# 02-MCU.net
KiCad netlist of a schematic drawn in Altium Designer
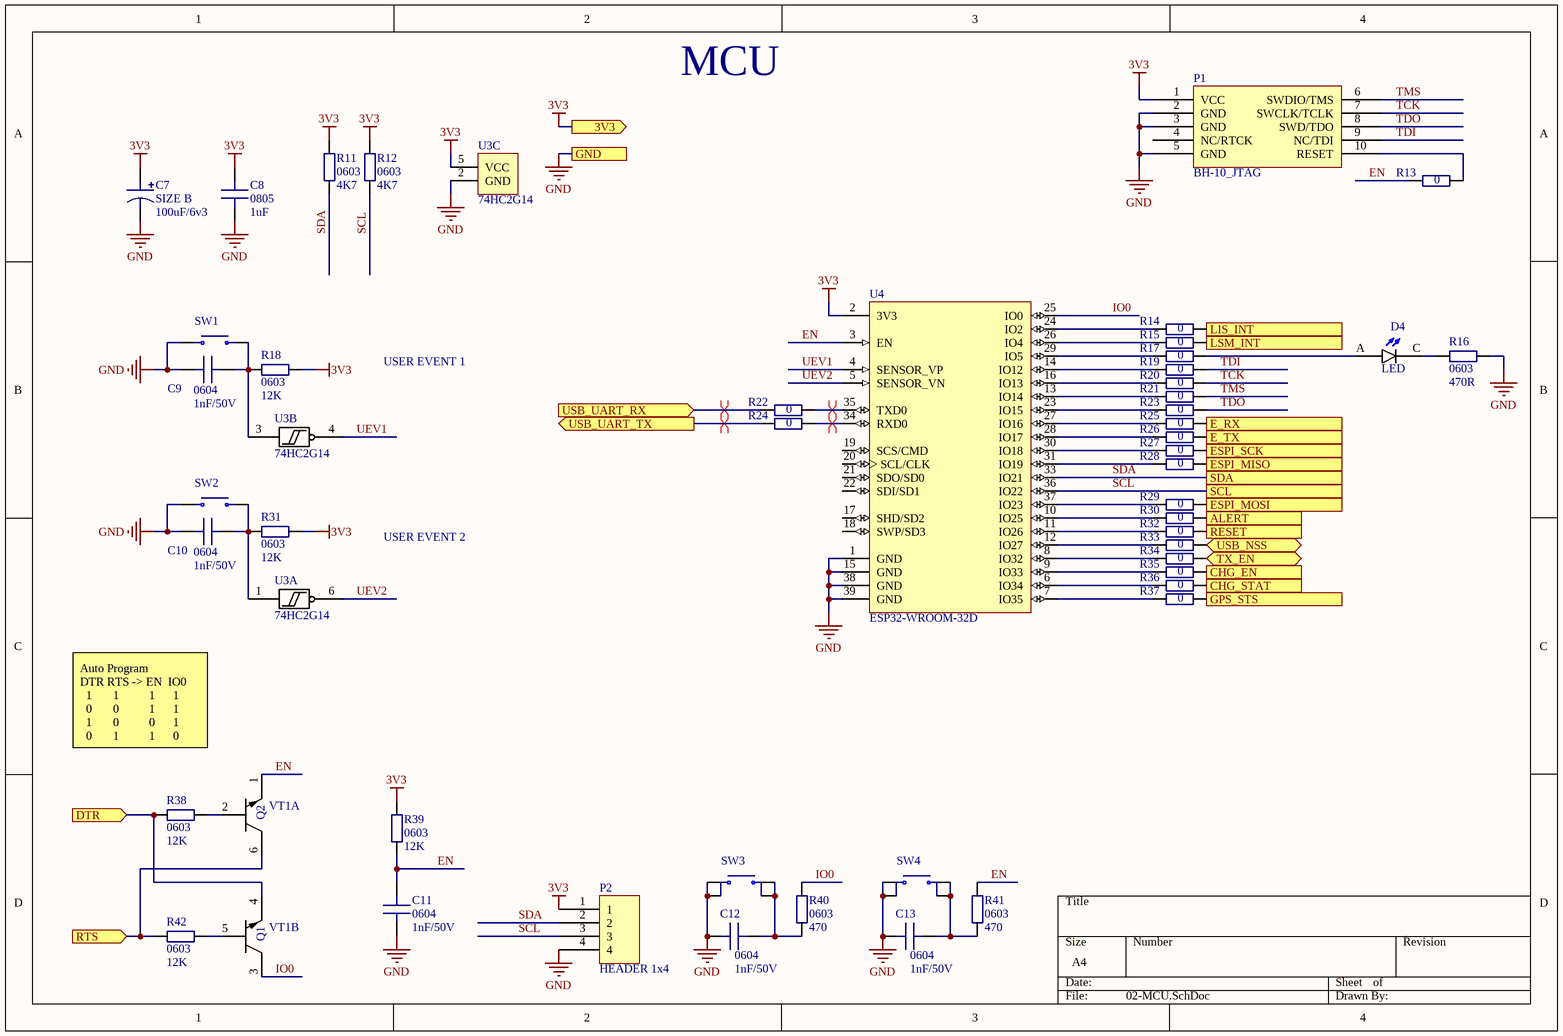
[diagram p0: 02-MCU.SchDoc]

(export (version "E")
  (design (tool "Eeschema 10.0.6"))
  (components
    (comp (ref "C7")
      (value "100uF/6v3")
      (footprint "CAP_SIZE_B")
      (description "General capacitor")
      (fields (field (name "SIZE") "SIZE B"))
      (libsource (lib "ComponentsLib") (part "C_GEN_POL_"))
    )
    (comp (ref "C8")
      (value "1uF")
      (footprint "C0805")
      (description "General capacitor")
      (fields (field (name "SIZE") "0805"))
      (libsource (lib "ComponentsLib") (part "C_GEN_NONPOL"))
    )
    (comp (ref "C9")
      (value "1nF/50V")
      (footprint "C0604")
      (description "General capacitor")
      (fields (field (name "SIZE") "0604"))
      (libsource (lib "ComponentsLib") (part "C_GEN_NONPOL"))
    )
    (comp (ref "C10")
      (value "1nF/50V")
      (footprint "C0604")
      (description "General capacitor")
      (fields (field (name "SIZE") "0604"))
      (libsource (lib "ComponentsLib") (part "C_GEN_NONPOL"))
    )
    (comp (ref "C11")
      (value "1nF/50V")
      (footprint "C0604")
      (description "General capacitor")
      (fields (field (name "SIZE") "0604"))
      (libsource (lib "ComponentsLib") (part "C_GEN_NONPOL"))
    )
    (comp (ref "C12")
      (value "1nF/50V")
      (footprint "C0604")
      (description "General capacitor")
      (fields (field (name "SIZE") "0604"))
      (libsource (lib "ComponentsLib") (part "C_GEN_NONPOL"))
    )
    (comp (ref "C13")
      (value "1nF/50V")
      (footprint "C0604")
      (description "General capacitor")
      (fields (field (name "SIZE") "0604"))
      (libsource (lib "ComponentsLib") (part "C_GEN_NONPOL"))
    )
    (comp (ref "D4")
      (value "LED")
      (footprint "LED_0604")
      (description "Led General")
      (fields (field (name "MF") "Dialight") (field (name "MP") "598-8140-107F"))
      (libsource (lib "ComponentsLib") (part "LED"))
    )
    (comp (ref "P1")
      (value "BH-10_JTAG")
      (footprint "BH-10R")
      (libsource (lib "ComponentsLib") (part "BH-10_JTAG"))
    )
    (comp (ref "P2")
      (value "HEADER 1x4")
      (footprint "HEADER 1x4 2.54")
      (libsource (lib "ComponentsLib") (part "HEADER 1x4"))
    )
    (comp (ref "R11")
      (value "~")
      (footprint "R0604")
      (description "Resistor General")
      (fields (field (name "SIZE") "0603") (field (name "RESISTANCE") "4K7"))
      (libsource (lib "ComponentsLib") (part "R_GENERAL"))
    )
    (comp (ref "R12")
      (value "~")
      (footprint "R0604")
      (description "Resistor General")
      (fields (field (name "SIZE") "0603") (field (name "RESISTANCE") "4K7"))
      (libsource (lib "ComponentsLib") (part "R_GENERAL"))
    )
    (comp (ref "R13")
      (value "~")
      (footprint "R0402")
      (description "Resistor General")
      (fields (field (name "RESISTANCE") "0"))
      (libsource (lib "ComponentsLib") (part "R_GENERAL"))
    )
    (comp (ref "R14")
      (value "~")
      (footprint "R0402")
      (description "Resistor General")
      (fields (field (name "RESISTANCE") "0"))
      (libsource (lib "ComponentsLib") (part "R_GENERAL"))
    )
    (comp (ref "R15")
      (value "~")
      (footprint "R0402")
      (description "Resistor General")
      (fields (field (name "RESISTANCE") "0"))
      (libsource (lib "ComponentsLib") (part "R_GENERAL"))
    )
    (comp (ref "R16")
      (value "~")
      (footprint "R0604")
      (description "Resistor General")
      (fields (field (name "SIZE") "0603") (field (name "RESISTANCE") "470R"))
      (libsource (lib "ComponentsLib") (part "R_GENERAL"))
    )
    (comp (ref "R17")
      (value "~")
      (footprint "R0402")
      (description "Resistor General")
      (fields (field (name "RESISTANCE") "0"))
      (libsource (lib "ComponentsLib") (part "R_GENERAL"))
    )
    (comp (ref "R18")
      (value "~")
      (footprint "R0604")
      (description "Resistor General")
      (fields (field (name "SIZE") "0603") (field (name "RESISTANCE") "12K"))
      (libsource (lib "ComponentsLib") (part "R_GENERAL"))
    )
    (comp (ref "R19")
      (value "~")
      (footprint "R0402")
      (description "Resistor General")
      (fields (field (name "RESISTANCE") "0"))
      (libsource (lib "ComponentsLib") (part "R_GENERAL"))
    )
    (comp (ref "R20")
      (value "~")
      (footprint "R0402")
      (description "Resistor General")
      (fields (field (name "RESISTANCE") "0"))
      (libsource (lib "ComponentsLib") (part "R_GENERAL"))
    )
    (comp (ref "R21")
      (value "~")
      (footprint "R0402")
      (description "Resistor General")
      (fields (field (name "RESISTANCE") "0"))
      (libsource (lib "ComponentsLib") (part "R_GENERAL"))
    )
    (comp (ref "R22")
      (value "~")
      (footprint "R0402")
      (description "Resistor General")
      (fields (field (name "RESISTANCE") "0"))
      (libsource (lib "ComponentsLib") (part "R_GENERAL"))
    )
    (comp (ref "R23")
      (value "~")
      (footprint "R0402")
      (description "Resistor General")
      (fields (field (name "RESISTANCE") "0"))
      (libsource (lib "ComponentsLib") (part "R_GENERAL"))
    )
    (comp (ref "R24")
      (value "~")
      (footprint "R0402")
      (description "Resistor General")
      (fields (field (name "RESISTANCE") "0"))
      (libsource (lib "ComponentsLib") (part "R_GENERAL"))
    )
    (comp (ref "R25")
      (value "~")
      (footprint "R0402")
      (description "Resistor General")
      (fields (field (name "RESISTANCE") "0"))
      (libsource (lib "ComponentsLib") (part "R_GENERAL"))
    )
    (comp (ref "R26")
      (value "~")
      (footprint "R0402")
      (description "Resistor General")
      (fields (field (name "RESISTANCE") "0"))
      (libsource (lib "ComponentsLib") (part "R_GENERAL"))
    )
    (comp (ref "R27")
      (value "~")
      (footprint "R0402")
      (description "Resistor General")
      (fields (field (name "RESISTANCE") "0"))
      (libsource (lib "ComponentsLib") (part "R_GENERAL"))
    )
    (comp (ref "R28")
      (value "~")
      (footprint "R0402")
      (description "Resistor General")
      (fields (field (name "RESISTANCE") "0"))
      (libsource (lib "ComponentsLib") (part "R_GENERAL"))
    )
    (comp (ref "R29")
      (value "~")
      (footprint "R0402")
      (description "Resistor General")
      (fields (field (name "RESISTANCE") "0"))
      (libsource (lib "ComponentsLib") (part "R_GENERAL"))
    )
    (comp (ref "R30")
      (value "~")
      (footprint "R0402")
      (description "Resistor General")
      (fields (field (name "RESISTANCE") "0"))
      (libsource (lib "ComponentsLib") (part "R_GENERAL"))
    )
    (comp (ref "R31")
      (value "~")
      (footprint "R0604")
      (description "Resistor General")
      (fields (field (name "SIZE") "0603") (field (name "RESISTANCE") "12K"))
      (libsource (lib "ComponentsLib") (part "R_GENERAL"))
    )
    (comp (ref "R32")
      (value "~")
      (footprint "R0402")
      (description "Resistor General")
      (fields (field (name "RESISTANCE") "0"))
      (libsource (lib "ComponentsLib") (part "R_GENERAL"))
    )
    (comp (ref "R33")
      (value "~")
      (footprint "R0402")
      (description "Resistor General")
      (fields (field (name "RESISTANCE") "0"))
      (libsource (lib "ComponentsLib") (part "R_GENERAL"))
    )
    (comp (ref "R34")
      (value "~")
      (footprint "R0402")
      (description "Resistor General")
      (fields (field (name "RESISTANCE") "0"))
      (libsource (lib "ComponentsLib") (part "R_GENERAL"))
    )
    (comp (ref "R35")
      (value "~")
      (footprint "R0402")
      (description "Resistor General")
      (fields (field (name "RESISTANCE") "0"))
      (libsource (lib "ComponentsLib") (part "R_GENERAL"))
    )
    (comp (ref "R36")
      (value "~")
      (footprint "R0402")
      (description "Resistor General")
      (fields (field (name "RESISTANCE") "0"))
      (libsource (lib "ComponentsLib") (part "R_GENERAL"))
    )
    (comp (ref "R37")
      (value "~")
      (footprint "R0604")
      (description "Resistor General")
      (fields (field (name "RESISTANCE") "0"))
      (libsource (lib "ComponentsLib") (part "R_GENERAL"))
    )
    (comp (ref "R38")
      (value "~")
      (footprint "R0604")
      (description "Resistor General")
      (fields (field (name "SIZE") "0603") (field (name "RESISTANCE") "12K"))
      (libsource (lib "ComponentsLib") (part "R_GENERAL"))
    )
    (comp (ref "R39")
      (value "~")
      (footprint "R0604")
      (description "Resistor General")
      (fields (field (name "SIZE") "0603") (field (name "RESISTANCE") "12K"))
      (libsource (lib "ComponentsLib") (part "R_GENERAL"))
    )
    (comp (ref "R40")
      (value "~")
      (footprint "R0604")
      (description "Resistor General")
      (fields (field (name "SIZE") "0603") (field (name "RESISTANCE") "470"))
      (libsource (lib "ComponentsLib") (part "R_GENERAL"))
    )
    (comp (ref "R41")
      (value "~")
      (footprint "R0604")
      (description "Resistor General")
      (fields (field (name "SIZE") "0603") (field (name "RESISTANCE") "470"))
      (libsource (lib "ComponentsLib") (part "R_GENERAL"))
    )
    (comp (ref "R42")
      (value "~")
      (footprint "R0604")
      (description "Resistor General")
      (fields (field (name "SIZE") "0603") (field (name "RESISTANCE") "12K"))
      (libsource (lib "ComponentsLib") (part "R_GENERAL"))
    )
    (comp (ref "SW1")
      (value "SWITCH_GEN_2P")
      (footprint "SW_GENERIC-SIDE")
      (description "SWITCH DIP 4.3 mm")
      (libsource (lib "ComponentsLib") (part "SWITCH_GEN_2P"))
    )
    (comp (ref "SW2")
      (value "SWITCH_GEN_2P")
      (footprint "SW_GENERIC-SIDE")
      (description "SWITCH DIP 4.3 mm")
      (libsource (lib "ComponentsLib") (part "SWITCH_GEN_2P"))
    )
    (comp (ref "SW3")
      (value "SWITCH_GEN_4P")
      (footprint "SW_4x4x1.5")
      (description "SWITCH DIP 4.3 mm")
      (libsource (lib "ComponentsLib") (part "SWITCH_GEN_4P"))
    )
    (comp (ref "SW4")
      (value "SWITCH_GEN_4P")
      (footprint "SW_4x4x1.5")
      (description "SWITCH DIP 4.3 mm")
      (libsource (lib "ComponentsLib") (part "SWITCH_GEN_4P"))
    )
    (comp (ref "U3")
      (value "74HC2G14")
      (footprint "SOT363/SOT65P210X110-6N")
      (libsource (lib "ComponentsLib") (part "74HC2G14"))
    )
    (comp (ref "U4")
      (value "ESP32-WROOM-32D")
      (footprint "ESP32-WROOM-32")
      (description "IC: SoC; GPIO, I2C, I2S, IR, SD, SDIO, SPI, UART; 2.7Г·3.6VDC; 20dBm")
      (fields (field (name "MF") "Espressif Systems"))
      (libsource (lib "ComponentsLib") (part "ESP32-WROOM-32D"))
    )
    (comp (ref "VT1")
      (value "BC847BDW1T1G")
      (footprint "SOT363/SOT65P210X110-6N")
      (libsource (lib "ComponentsLib") (part "BC847BDW1T1G"))
    )
  )
  (nets
    (net (code "1") (name "/ALERT") (class "Default")
      (node (ref "R30") (pin "2") (pinfunction "2_2") (pintype "passive"))
    )
    (net (code "2") (name "/CHG_EN") (class "Default")
      (node (ref "R35") (pin "2") (pinfunction "2_2") (pintype "passive"))
    )
    (net (code "3") (name "/CHG_STAT") (class "Default")
      (node (ref "R36") (pin "2") (pinfunction "2_2") (pintype "passive"))
    )
    (net (code "4") (name "/DTR") (class "Default")
      (node (ref "R38") (pin "2") (pinfunction "2_2") (pintype "passive"))
      (node (ref "VT1") (pin "4") (pinfunction "4_4") (pintype "passive"))
    )
    (net (code "5") (name "/EN") (class "Default")
      (node (ref "C11") (pin "2") (pinfunction "2_2") (pintype "passive"))
      (node (ref "R13") (pin "1") (pinfunction "1_1") (pintype "passive"))
      (node (ref "R39") (pin "2") (pinfunction "2_2") (pintype "passive"))
      (node (ref "R41") (pin "2") (pinfunction "2_2") (pintype "passive"))
      (node (ref "U4") (pin "3") (pinfunction "EN_3") (pintype "input"))
      (node (ref "VT1") (pin "1") (pinfunction "1_1") (pintype "passive"))
    )
    (net (code "6") (name "/ESPI_MISO") (class "Default")
      (node (ref "R28") (pin "2") (pinfunction "2_2") (pintype "passive"))
    )
    (net (code "7") (name "/ESPI_MOSI") (class "Default")
      (node (ref "R29") (pin "2") (pinfunction "2_2") (pintype "passive"))
    )
    (net (code "8") (name "/ESPI_SCK") (class "Default")
      (node (ref "R27") (pin "2") (pinfunction "2_2") (pintype "passive"))
    )
    (net (code "9") (name "/E_RX") (class "Default")
      (node (ref "R25") (pin "2") (pinfunction "2_2") (pintype "passive"))
    )
    (net (code "10") (name "/E_TX") (class "Default")
      (node (ref "R26") (pin "2") (pinfunction "2_2") (pintype "passive"))
    )
    (net (code "11") (name "/GPS_STS") (class "Default")
      (node (ref "R37") (pin "2") (pinfunction "2_2") (pintype "passive"))
    )
    (net (code "12") (name "/IO0") (class "Default")
      (node (ref "R40") (pin "2") (pinfunction "2_2") (pintype "passive"))
      (node (ref "U4") (pin "25") (pinfunction "IO0_25") (pintype "bidirectional"))
      (node (ref "VT1") (pin "3") (pinfunction "3_3") (pintype "passive"))
    )
    (net (code "13") (name "/LIS_INT") (class "Default")
      (node (ref "R14") (pin "2") (pinfunction "2_2") (pintype "passive"))
    )
    (net (code "14") (name "/LSM_INT") (class "Default")
      (node (ref "R15") (pin "2") (pinfunction "2_2") (pintype "passive"))
    )
    (net (code "15") (name "/RESET") (class "Default")
      (node (ref "R32") (pin "2") (pinfunction "2_2") (pintype "passive"))
    )
    (net (code "16") (name "/RTS") (class "Default")
      (node (ref "R42") (pin "2") (pinfunction "2_2") (pintype "passive"))
      (node (ref "VT1") (pin "6") (pinfunction "6_6") (pintype "passive"))
    )
    (net (code "17") (name "/SCL") (class "Default")
      (node (ref "P2") (pin "3") (pinfunction "3_3") (pintype "passive"))
      (node (ref "R12") (pin "2") (pinfunction "2_2") (pintype "passive"))
      (node (ref "U4") (pin "36") (pinfunction "IO22_36") (pintype "bidirectional"))
    )
    (net (code "18") (name "/SDA") (class "Default")
      (node (ref "P2") (pin "2") (pinfunction "2_2") (pintype "passive"))
      (node (ref "R11") (pin "2") (pinfunction "2_2") (pintype "passive"))
      (node (ref "U4") (pin "33") (pinfunction "IO21_33") (pintype "bidirectional"))
    )
    (net (code "19") (name "/TCK") (class "Default")
      (node (ref "P1") (pin "7") (pinfunction "SWCLK/TCLK_7") (pintype "passive"))
      (node (ref "R20") (pin "2") (pinfunction "2_2") (pintype "passive"))
    )
    (net (code "20") (name "/TDI") (class "Default")
      (node (ref "P1") (pin "9") (pinfunction "NC/TDI_9") (pintype "passive"))
      (node (ref "R19") (pin "2") (pinfunction "2_2") (pintype "passive"))
    )
    (net (code "21") (name "/TDO") (class "Default")
      (node (ref "P1") (pin "8") (pinfunction "SWD/TDO_8") (pintype "passive"))
      (node (ref "R23") (pin "2") (pinfunction "2_2") (pintype "passive"))
    )
    (net (code "22") (name "/TMS") (class "Default")
      (node (ref "P1") (pin "6") (pinfunction "SWDIO/TMS_6") (pintype "passive"))
      (node (ref "R21") (pin "2") (pinfunction "2_2") (pintype "passive"))
    )
    (net (code "23") (name "/TX_EN") (class "Default")
      (node (ref "R34") (pin "2") (pinfunction "2_2") (pintype "passive"))
    )
    (net (code "24") (name "/UEV1") (class "Default")
      (node (ref "U3") (pin "4") (pinfunction "2Y_4") (pintype "passive"))
      (node (ref "U4") (pin "4") (pinfunction "SENSOR_VP_4") (pintype "input"))
    )
    (net (code "25") (name "/UEV2") (class "Default")
      (node (ref "U3") (pin "6") (pinfunction "1Y_6") (pintype "passive"))
      (node (ref "U4") (pin "5") (pinfunction "SENSOR_VN_5") (pintype "input"))
    )
    (net (code "26") (name "/USB_NSS") (class "Default")
      (node (ref "R33") (pin "2") (pinfunction "2_2") (pintype "passive"))
    )
    (net (code "27") (name "/USB_UART_RX") (class "Default")
      (node (ref "R22") (pin "1") (pinfunction "1_1") (pintype "passive"))
    )
    (net (code "28") (name "/USB_UART_TX") (class "Default")
      (node (ref "R24") (pin "1") (pinfunction "1_1") (pintype "passive"))
    )
    (net (code "29") (name "3V3") (class "Default")
      (node (ref "C7") (pin "1") (pinfunction "1_1") (pintype "passive"))
      (node (ref "C8") (pin "2") (pinfunction "2_2") (pintype "passive"))
      (node (ref "P1") (pin "1") (pinfunction "VCC_1") (pintype "passive"))
      (node (ref "P2") (pin "1") (pinfunction "1_1") (pintype "passive"))
      (node (ref "R11") (pin "1") (pinfunction "1_1") (pintype "passive"))
      (node (ref "R12") (pin "1") (pinfunction "1_1") (pintype "passive"))
      (node (ref "R18") (pin "1") (pinfunction "1_1") (pintype "passive"))
      (node (ref "R31") (pin "1") (pinfunction "1_1") (pintype "passive"))
      (node (ref "R39") (pin "1") (pinfunction "1_1") (pintype "passive"))
      (node (ref "U3") (pin "5") (pinfunction "VCC_5") (pintype "passive"))
      (node (ref "U4") (pin "2") (pinfunction "3V3_2") (pintype "power_in"))
    )
    (net (code "30") (name "GND") (class "Default")
      (node (ref "C10") (pin "1") (pinfunction "1_1") (pintype "passive"))
      (node (ref "C11") (pin "1") (pinfunction "1_1") (pintype "passive"))
      (node (ref "C12") (pin "1") (pinfunction "1_1") (pintype "passive"))
      (node (ref "C13") (pin "1") (pinfunction "1_1") (pintype "passive"))
      (node (ref "C7") (pin "2") (pinfunction "2_2") (pintype "passive"))
      (node (ref "C8") (pin "1") (pinfunction "1_1") (pintype "passive"))
      (node (ref "C9") (pin "1") (pinfunction "1_1") (pintype "passive"))
      (node (ref "P1") (pin "2") (pinfunction "GND_2") (pintype "passive"))
      (node (ref "P1") (pin "3") (pinfunction "GND_3") (pintype "passive"))
      (node (ref "P1") (pin "5") (pinfunction "GND_5") (pintype "passive"))
      (node (ref "P2") (pin "4") (pinfunction "4_4") (pintype "passive"))
      (node (ref "R16") (pin "1") (pinfunction "1_1") (pintype "passive"))
      (node (ref "SW1") (pin "1") (pinfunction "1_1") (pintype "passive"))
      (node (ref "SW2") (pin "1") (pinfunction "1_1") (pintype "passive"))
      (node (ref "SW3") (pin "1") (pinfunction "1_1") (pintype "passive"))
      (node (ref "SW3") (pin "3") (pinfunction "3_3") (pintype "passive"))
      (node (ref "SW4") (pin "1") (pinfunction "1_1") (pintype "passive"))
      (node (ref "SW4") (pin "3") (pinfunction "3_3") (pintype "passive"))
      (node (ref "U3") (pin "2") (pinfunction "GND_2") (pintype "passive"))
      (node (ref "U4") (pin "1") (pinfunction "GND_1") (pintype "power_in"))
      (node (ref "U4") (pin "15") (pinfunction "GND_15") (pintype "power_in"))
      (node (ref "U4") (pin "38") (pinfunction "GND_38") (pintype "power_in"))
      (node (ref "U4") (pin "39") (pinfunction "GND_39") (pintype "power_in"))
    )
    (net (code "31") (name "Net-(C12-Pad2)") (class "Default")
      (node (ref "C12") (pin "2") (pinfunction "2_2") (pintype "passive"))
      (node (ref "R40") (pin "1") (pinfunction "1_1") (pintype "passive"))
      (node (ref "SW3") (pin "2") (pinfunction "2_2") (pintype "passive"))
      (node (ref "SW3") (pin "4") (pinfunction "4_4") (pintype "passive"))
    )
    (net (code "32") (name "Net-(C13-Pad2)") (class "Default")
      (node (ref "C13") (pin "2") (pinfunction "2_2") (pintype "passive"))
      (node (ref "R41") (pin "1") (pinfunction "1_1") (pintype "passive"))
      (node (ref "SW4") (pin "2") (pinfunction "2_2") (pintype "passive"))
      (node (ref "SW4") (pin "4") (pinfunction "4_4") (pintype "passive"))
    )
    (net (code "33") (name "Net-(D4-PadA)") (class "Default")
      (node (ref "D4") (pin "A") (pinfunction "A_A") (pintype "passive"))
      (node (ref "R17") (pin "2") (pinfunction "2_2") (pintype "passive"))
    )
    (net (code "34") (name "Net-(D4-PadC)") (class "Default")
      (node (ref "D4") (pin "C") (pinfunction "C_C") (pintype "passive"))
      (node (ref "R16") (pin "2") (pinfunction "2_2") (pintype "passive"))
    )
    (net (code "35") (name "Net-(P1-RESET)") (class "Default")
      (node (ref "P1") (pin "10") (pinfunction "RESET_10") (pintype "passive"))
      (node (ref "R13") (pin "2") (pinfunction "2_2") (pintype "passive"))
    )
    (net (code "36") (name "Net-(R38-Pad1)") (class "Default")
      (node (ref "R38") (pin "1") (pinfunction "1_1") (pintype "passive"))
      (node (ref "VT1") (pin "2") (pinfunction "2_2") (pintype "passive"))
    )
    (net (code "37") (name "Net-(R42-Pad1)") (class "Default")
      (node (ref "R42") (pin "1") (pinfunction "1_1") (pintype "passive"))
      (node (ref "VT1") (pin "5") (pinfunction "5_5") (pintype "passive"))
    )
    (net (code "38") (name "Net-(U3A-1A)") (class "Default")
      (node (ref "C10") (pin "2") (pinfunction "2_2") (pintype "passive"))
      (node (ref "R31") (pin "2") (pinfunction "2_2") (pintype "passive"))
      (node (ref "SW2") (pin "2") (pinfunction "2_2") (pintype "passive"))
      (node (ref "U3") (pin "1") (pinfunction "1A_1") (pintype "passive"))
    )
    (net (code "39") (name "Net-(U3B-2A)") (class "Default")
      (node (ref "C9") (pin "2") (pinfunction "2_2") (pintype "passive"))
      (node (ref "R18") (pin "2") (pinfunction "2_2") (pintype "passive"))
      (node (ref "SW1") (pin "2") (pinfunction "2_2") (pintype "passive"))
      (node (ref "U3") (pin "3") (pinfunction "2A_3") (pintype "passive"))
    )
    (net (code "40") (name "Net-(U4-IO2)") (class "Default")
      (node (ref "R14") (pin "1") (pinfunction "1_1") (pintype "passive"))
      (node (ref "U4") (pin "24") (pinfunction "IO2_24") (pintype "bidirectional"))
    )
    (net (code "41") (name "Net-(U4-IO4)") (class "Default")
      (node (ref "R15") (pin "1") (pinfunction "1_1") (pintype "passive"))
      (node (ref "U4") (pin "26") (pinfunction "IO4_26") (pintype "bidirectional"))
    )
    (net (code "42") (name "Net-(U4-IO5)") (class "Default")
      (node (ref "R17") (pin "1") (pinfunction "1_1") (pintype "passive"))
      (node (ref "U4") (pin "29") (pinfunction "IO5_29") (pintype "bidirectional"))
    )
    (net (code "43") (name "Net-(U4-IO12)") (class "Default")
      (node (ref "R19") (pin "1") (pinfunction "1_1") (pintype "passive"))
      (node (ref "U4") (pin "14") (pinfunction "IO12_14") (pintype "bidirectional"))
    )
    (net (code "44") (name "Net-(U4-IO13)") (class "Default")
      (node (ref "R20") (pin "1") (pinfunction "1_1") (pintype "passive"))
      (node (ref "U4") (pin "16") (pinfunction "IO13_16") (pintype "bidirectional"))
    )
    (net (code "45") (name "Net-(U4-IO14)") (class "Default")
      (node (ref "R21") (pin "1") (pinfunction "1_1") (pintype "passive"))
      (node (ref "U4") (pin "13") (pinfunction "IO14_13") (pintype "bidirectional"))
    )
    (net (code "46") (name "Net-(U4-IO15)") (class "Default")
      (node (ref "R23") (pin "1") (pinfunction "1_1") (pintype "passive"))
      (node (ref "U4") (pin "23") (pinfunction "IO15_23") (pintype "bidirectional"))
    )
    (net (code "47") (name "Net-(U4-IO16)") (class "Default")
      (node (ref "R25") (pin "1") (pinfunction "1_1") (pintype "passive"))
      (node (ref "U4") (pin "27") (pinfunction "IO16_27") (pintype "bidirectional"))
    )
    (net (code "48") (name "Net-(U4-IO17)") (class "Default")
      (node (ref "R26") (pin "1") (pinfunction "1_1") (pintype "passive"))
      (node (ref "U4") (pin "28") (pinfunction "IO17_28") (pintype "bidirectional"))
    )
    (net (code "49") (name "Net-(U4-IO18)") (class "Default")
      (node (ref "R27") (pin "1") (pinfunction "1_1") (pintype "passive"))
      (node (ref "U4") (pin "30") (pinfunction "IO18_30") (pintype "bidirectional"))
    )
    (net (code "50") (name "Net-(U4-IO19)") (class "Default")
      (node (ref "R28") (pin "1") (pinfunction "1_1") (pintype "passive"))
      (node (ref "U4") (pin "31") (pinfunction "IO19_31") (pintype "bidirectional"))
    )
    (net (code "51") (name "Net-(U4-IO23)") (class "Default")
      (node (ref "R29") (pin "1") (pinfunction "1_1") (pintype "passive"))
      (node (ref "U4") (pin "37") (pinfunction "IO23_37") (pintype "bidirectional"))
    )
    (net (code "52") (name "Net-(U4-IO25)") (class "Default")
      (node (ref "R30") (pin "1") (pinfunction "1_1") (pintype "passive"))
      (node (ref "U4") (pin "10") (pinfunction "IO25_10") (pintype "bidirectional"))
    )
    (net (code "53") (name "Net-(U4-IO26)") (class "Default")
      (node (ref "R32") (pin "1") (pinfunction "1_1") (pintype "passive"))
      (node (ref "U4") (pin "11") (pinfunction "IO26_11") (pintype "bidirectional"))
    )
    (net (code "54") (name "Net-(U4-IO27)") (class "Default")
      (node (ref "R33") (pin "1") (pinfunction "1_1") (pintype "passive"))
      (node (ref "U4") (pin "12") (pinfunction "IO27_12") (pintype "bidirectional"))
    )
    (net (code "55") (name "Net-(U4-IO32)") (class "Default")
      (node (ref "R34") (pin "1") (pinfunction "1_1") (pintype "passive"))
      (node (ref "U4") (pin "8") (pinfunction "IO32_8") (pintype "bidirectional"))
    )
    (net (code "56") (name "Net-(U4-IO33)") (class "Default")
      (node (ref "R35") (pin "1") (pinfunction "1_1") (pintype "passive"))
      (node (ref "U4") (pin "9") (pinfunction "IO33_9") (pintype "bidirectional"))
    )
    (net (code "57") (name "Net-(U4-IO34)") (class "Default")
      (node (ref "R36") (pin "1") (pinfunction "1_1") (pintype "passive"))
      (node (ref "U4") (pin "6") (pinfunction "IO34_6") (pintype "bidirectional"))
    )
    (net (code "58") (name "Net-(U4-IO35)") (class "Default")
      (node (ref "R37") (pin "1") (pinfunction "1_1") (pintype "passive"))
      (node (ref "U4") (pin "7") (pinfunction "IO35_7") (pintype "bidirectional"))
    )
    (net (code "59") (name "Net-(U4-RXD0)") (class "Default")
      (node (ref "R24") (pin "2") (pinfunction "2_2") (pintype "passive"))
      (node (ref "U4") (pin "34") (pinfunction "RXD0_34") (pintype "bidirectional"))
    )
    (net (code "60") (name "Net-(U4-TXD0)") (class "Default")
      (node (ref "R22") (pin "2") (pinfunction "2_2") (pintype "passive"))
      (node (ref "U4") (pin "35") (pinfunction "TXD0_35") (pintype "bidirectional"))
    )
    (net (code "61") (name "unconnected-(P1-NC{slash}RTCK-Pad4)") (class "Default")
      (node (ref "P1") (pin "4") (pinfunction "NC/RTCK_4") (pintype "passive"))
    )
    (net (code "62") (name "unconnected-(U4-SCL{slash}CLK-Pad20)") (class "Default")
      (node (ref "U4") (pin "20") (pinfunction "SCL/CLK_20") (pintype "bidirectional"))
    )
    (net (code "63") (name "unconnected-(U4-SCS{slash}CMD-Pad19)") (class "Default")
      (node (ref "U4") (pin "19") (pinfunction "SCS/CMD_19") (pintype "bidirectional"))
    )
    (net (code "64") (name "unconnected-(U4-SDI{slash}SD1-Pad22)") (class "Default")
      (node (ref "U4") (pin "22") (pinfunction "SDI/SD1_22") (pintype "bidirectional"))
    )
    (net (code "65") (name "unconnected-(U4-SDO{slash}SD0-Pad21)") (class "Default")
      (node (ref "U4") (pin "21") (pinfunction "SDO/SD0_21") (pintype "bidirectional"))
    )
    (net (code "66") (name "unconnected-(U4-SHD{slash}SD2-Pad17)") (class "Default")
      (node (ref "U4") (pin "17") (pinfunction "SHD/SD2_17") (pintype "bidirectional"))
    )
    (net (code "67") (name "unconnected-(U4-SWP{slash}SD3-Pad18)") (class "Default")
      (node (ref "U4") (pin "18") (pinfunction "SWP/SD3_18") (pintype "bidirectional"))
    )
  )
)
